# main.net
KiCad netlist of a schematic drawn in Altium Designer
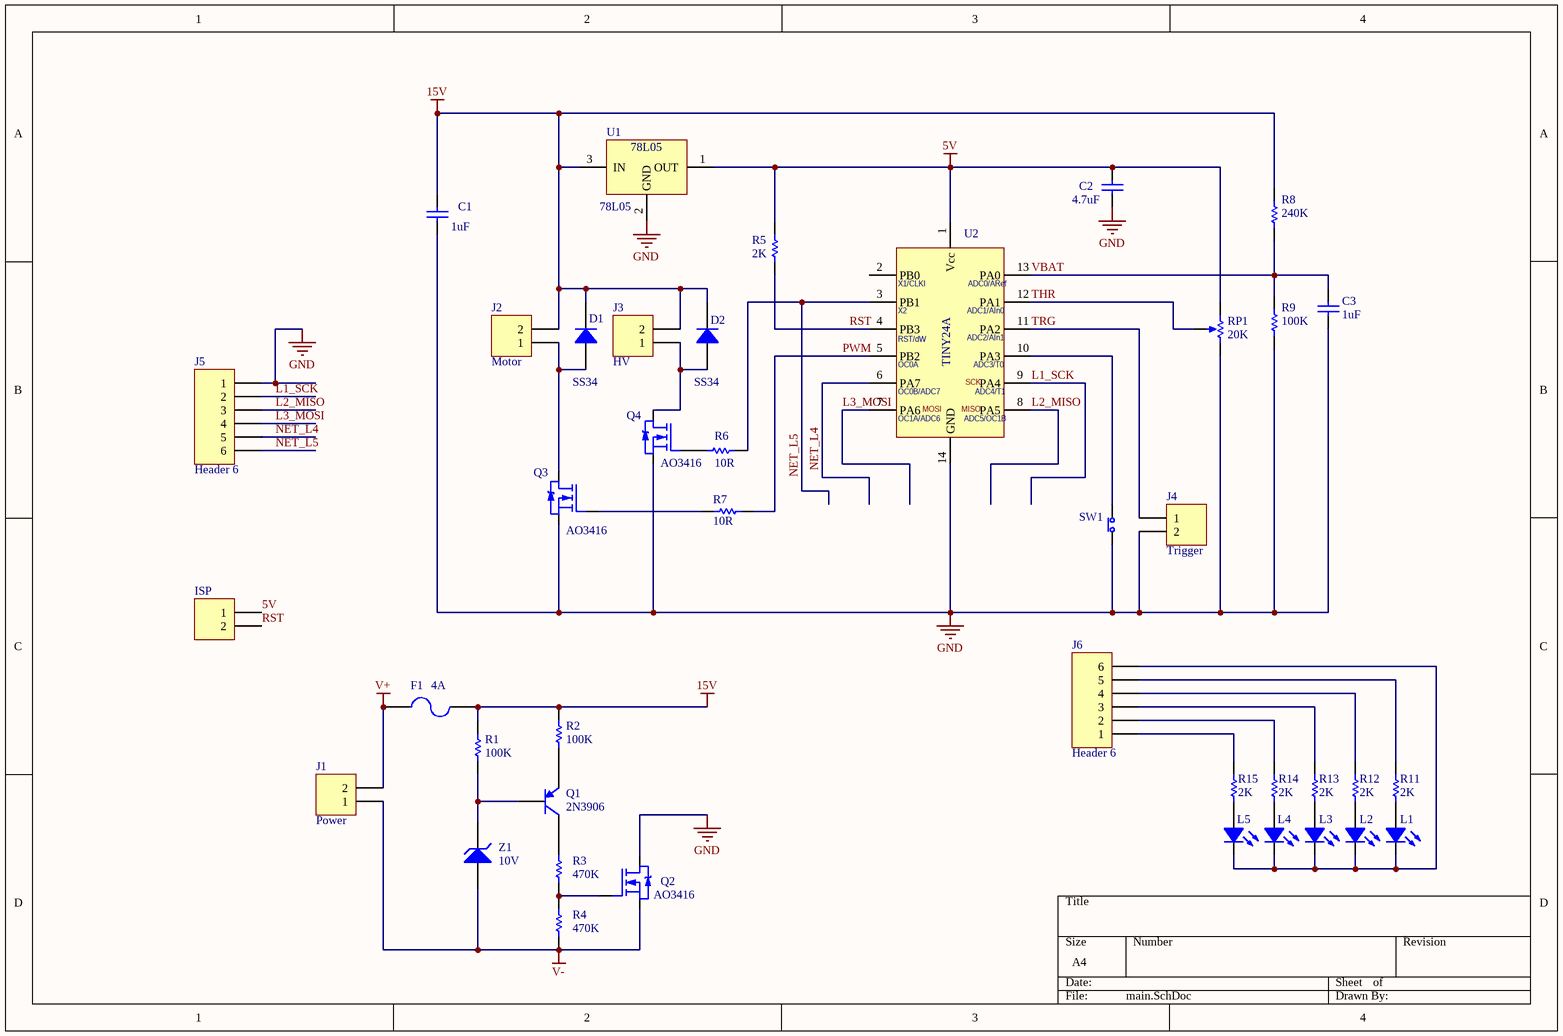
[diagram p0: main.SchDoc]

(export (version "E")
  (design (tool "Eeschema 10.0.6"))
  (components
    (comp (ref "C1")
      (value "1uF")
      (footprint "CAP0805")
      (description "贴片电容")
      (fields (field (name "Comment") "Cap") (field (name "PUBLISHER") "Altium Limited"))
      (libsource (lib "Miscellaneous Devices") (part "Cap"))
    )
    (comp (ref "C2")
      (value "4.7uF")
      (footprint "CAP0805")
      (description "贴片电容")
      (fields (field (name "Comment") "Cap") (field (name "PUBLISHER") "Altium Limited"))
      (libsource (lib "Miscellaneous Devices") (part "Cap"))
    )
    (comp (ref "C3")
      (value "1uF")
      (footprint "CAP0805")
      (description "贴片电容")
      (fields (field (name "Comment") "Cap") (field (name "PUBLISHER") "Altium Limited"))
      (libsource (lib "Miscellaneous Devices") (part "Cap"))
    )
    (comp (ref "D1")
      (value "SS34")
      (footprint "DO214A")
      (description "贴片二极管")
      (fields (field (name "PUBLISHER") "Altium Limited"))
      (libsource (lib "nizn") (part "Diode"))
    )
    (comp (ref "D2")
      (value "SS34")
      (footprint "DO214A")
      (description "贴片二极管")
      (fields (field (name "PUBLISHER") "Altium Limited"))
      (libsource (lib "nizn") (part "Diode"))
    )
    (comp (ref "F1")
      (value "4A")
      (footprint "FUSE1206")
      (description "贴片熔断型保险丝")
      (fields (field (name "PUBLISHER") "Altium Limited"))
      (libsource (lib "pumpctrl") (part "Fuse 2"))
    )
    (comp (ref "ISP")
      (value "~")
      (footprint "HDR1X2")
      (description "空")
      (fields (field (name "PUBLISHER") "Altium Limited"))
      (libsource (lib "Miscellaneous Connectors") (part "Header 2"))
    )
    (comp (ref "J1")
      (value "Power")
      (footprint "JST2")
      (description "JST 2P 插座")
      (fields (field (name "PUBLISHER") "Altium Limited"))
      (libsource (lib "") (part "Header 2_1"))
    )
    (comp (ref "J2")
      (value "Motor")
      (footprint "JST2")
      (description "JST 2P 插座")
      (fields (field (name "PUBLISHER") "Altium Limited"))
      (libsource (lib "") (part "Header 2_1"))
    )
    (comp (ref "J3")
      (value "HV")
      (footprint "JST2")
      (description "JST 2P 插座")
      (fields (field (name "PUBLISHER") "Altium Limited"))
      (libsource (lib "") (part "Header 2_1"))
    )
    (comp (ref "J4")
      (value "Trigger")
      (footprint "JST2")
      (description "JST 2P 插座")
      (fields (field (name "PUBLISHER") "Altium Limited"))
      (libsource (lib "") (part "Header 2_2"))
    )
    (comp (ref "J5")
      (value "Header 6")
      (footprint "HDR125_6W")
      (description "1.25mm 6P 插座")
      (fields (field (name "PUBLISHER") "Altium Limited"))
      (libsource (lib "Miscellaneous Connectors") (part "Header 6"))
    )
    (comp (ref "J6")
      (value "Header 6")
      (footprint "HDR125_6W")
      (description "1.25mm 6P 插座")
      (fields (field (name "PUBLISHER") "Altium Limited"))
      (libsource (lib "") (part "Header 6_1"))
    )
    (comp (ref "L1")
      (value "高亮翠绿")
      (footprint "LED2G_SLIM")
      (description "贴片LED 0805")
      (fields (field (name "PUBLISHER") "Altium Limited"))
      (libsource (lib "pumpctrl") (part "LED"))
    )
    (comp (ref "L2")
      (value "高亮翠绿")
      (footprint "LED2G_SLIM")
      (description "贴片LED 0805")
      (fields (field (name "PUBLISHER") "Altium Limited"))
      (libsource (lib "pumpctrl") (part "LED"))
    )
    (comp (ref "L3")
      (value "高亮翠绿")
      (footprint "LED2G_SLIM")
      (description "贴片LED 0805")
      (fields (field (name "PUBLISHER") "Altium Limited"))
      (libsource (lib "pumpctrl") (part "LED"))
    )
    (comp (ref "L4")
      (value "高亮翠绿")
      (footprint "LED2G_SLIM")
      (description "贴片LED 0805")
      (fields (field (name "PUBLISHER") "Altium Limited"))
      (libsource (lib "pumpctrl") (part "LED"))
    )
    (comp (ref "L5")
      (value "高亮蓝色")
      (footprint "LED2R_SLIM")
      (description "贴片LED 0805")
      (fields (field (name "PUBLISHER") "Altium Limited"))
      (libsource (lib "pumpctrl") (part "LED"))
    )
    (comp (ref "Q1")
      (value "2N3906")
      (footprint "SOT23_CBE")
      (description "PNP General Purpose Amplifier")
      (fields (field (name "PUBLISHER") "Altium Limited"))
      (libsource (lib "pumpctrl") (part "PNP"))
    )
    (comp (ref "Q2")
      (value "AO3416")
      (footprint "SOT23_NMOS")
      (description "MOSFET N")
      (fields (field (name "PUBLISHER") "Altium Limited"))
      (libsource (lib "pumpctrl") (part "NMOS"))
    )
    (comp (ref "Q3")
      (value "AO3416")
      (footprint "SOT23_NMOS")
      (description "MOSFET N")
      (fields (field (name "PUBLISHER") "Altium Limited"))
      (libsource (lib "pumpctrl") (part "NMOS"))
    )
    (comp (ref "Q4")
      (value "AO3416")
      (footprint "SOT23_NMOS")
      (description "MOSFET N")
      (fields (field (name "PUBLISHER") "Altium Limited"))
      (libsource (lib "pumpctrl") (part "NMOS"))
    )
    (comp (ref "R1")
      (value "100K")
      (footprint "RES0805")
      (description "贴片电阻")
      (fields (field (name "Comment") "Res1") (field (name "PUBLISHER") "Altium Limited"))
      (libsource (lib "Miscellaneous Devices") (part "Res1"))
    )
    (comp (ref "R2")
      (value "100K")
      (footprint "RES0805")
      (description "贴片电阻")
      (fields (field (name "Comment") "Res1") (field (name "PUBLISHER") "Altium Limited"))
      (libsource (lib "Miscellaneous Devices") (part "Res1"))
    )
    (comp (ref "R3")
      (value "470K")
      (footprint "RES0805")
      (description "贴片电阻")
      (fields (field (name "Comment") "Res1") (field (name "PUBLISHER") "Altium Limited"))
      (libsource (lib "Miscellaneous Devices") (part "Res1"))
    )
    (comp (ref "R4")
      (value "470K")
      (footprint "RES0805")
      (description "贴片电阻")
      (fields (field (name "Comment") "Res1") (field (name "PUBLISHER") "Altium Limited"))
      (libsource (lib "Miscellaneous Devices") (part "Res1"))
    )
    (comp (ref "R5")
      (value "2K")
      (footprint "RES0805")
      (description "贴片电阻")
      (fields (field (name "Comment") "Res1") (field (name "PUBLISHER") "Altium Limited"))
      (libsource (lib "Miscellaneous Devices") (part "Res1"))
    )
    (comp (ref "R6")
      (value "10R")
      (footprint "RES0805")
      (description "贴片电阻")
      (fields (field (name "Comment") "Res1") (field (name "PUBLISHER") "Altium Limited"))
      (libsource (lib "Miscellaneous Devices") (part "Res1"))
    )
    (comp (ref "R7")
      (value "10R")
      (footprint "RES0805")
      (description "贴片电阻")
      (fields (field (name "Comment") "Res1") (field (name "PUBLISHER") "Altium Limited"))
      (libsource (lib "Miscellaneous Devices") (part "Res1"))
    )
    (comp (ref "R8")
      (value "240K")
      (footprint "RES0805")
      (description "贴片电阻")
      (fields (field (name "Comment") "Res1") (field (name "PUBLISHER") "Altium Limited"))
      (libsource (lib "Miscellaneous Devices") (part "Res1"))
    )
    (comp (ref "R9")
      (value "100K")
      (footprint "RES0805")
      (description "贴片电阻")
      (fields (field (name "Comment") "Res1") (field (name "PUBLISHER") "Altium Limited"))
      (libsource (lib "Miscellaneous Devices") (part "Res1"))
    )
    (comp (ref "R11")
      (value "2K")
      (footprint "RES0805")
      (description "贴片电阻")
      (fields (field (name "Comment") "Res1") (field (name "PUBLISHER") "Altium Limited"))
      (libsource (lib "Miscellaneous Devices") (part "Res1"))
    )
    (comp (ref "R12")
      (value "2K")
      (footprint "RES0805")
      (description "贴片电阻")
      (fields (field (name "Comment") "Res1") (field (name "PUBLISHER") "Altium Limited"))
      (libsource (lib "Miscellaneous Devices") (part "Res1"))
    )
    (comp (ref "R13")
      (value "2K")
      (footprint "RES0805")
      (description "贴片电阻")
      (fields (field (name "Comment") "Res1") (field (name "PUBLISHER") "Altium Limited"))
      (libsource (lib "Miscellaneous Devices") (part "Res1"))
    )
    (comp (ref "R14")
      (value "2K")
      (footprint "RES0805")
      (description "贴片电阻")
      (fields (field (name "Comment") "Res1") (field (name "PUBLISHER") "Altium Limited"))
      (libsource (lib "Miscellaneous Devices") (part "Res1"))
    )
    (comp (ref "R15")
      (value "2K")
      (footprint "RES0805")
      (description "贴片电阻")
      (fields (field (name "Comment") "Res1") (field (name "PUBLISHER") "Altium Limited"))
      (libsource (lib "Miscellaneous Devices") (part "Res1"))
    )
    (comp (ref "RP1")
      (value "20K")
      (footprint "POT_RV09")
      (description "Potentiometer")
      (fields (field (name "Comment") "RPot") (field (name "PUBLISHER") "Altium Limited"))
      (libsource (lib "Miscellaneous Devices") (part "RPot"))
    )
    (comp (ref "SW1")
      (value "~")
      (footprint "TACT2")
      (description "轻触开关")
      (fields (field (name "PUBLISHER") "Altium Limited"))
      (libsource (lib "pumpctrl") (part "JP2"))
    )
    (comp (ref "U1")
      (value "78L05")
      (footprint "SOT89_VREG")
      (description "三端稳压贴片")
      (fields (field (name "PUBLISHER") "Altium Limited"))
      (libsource (lib "magcontrol") (part "78L05"))
    )
    (comp (ref "U2")
      (value "TINY24A")
      (footprint "SO14")
      (description "集成电路")
      (libsource (lib "nizn") (part "TINY13A"))
    )
    (comp (ref "Z1")
      (value "10V")
      (footprint "1N4148SMT")
      (description "Zener Diode")
      (fields (field (name "PUBLISHER") "Altium Limited"))
      (libsource (lib "Miscellaneous Devices") (part "D Zener"))
    )
  )
  (nets
    (net (code "1") (name "/L1_SCK") (class "Default")
      (node (ref "J5") (pin "2") (pinfunction "2_2") (pintype "passive"))
      (node (ref "U2") (pin "9") (pinfunction "PA4_9") (pintype "power_in"))
    )
    (net (code "2") (name "/L2_MISO") (class "Default")
      (node (ref "J5") (pin "3") (pinfunction "3_3") (pintype "passive"))
      (node (ref "U2") (pin "8") (pinfunction "PA5_8") (pintype "power_in"))
    )
    (net (code "3") (name "/L3_MOSI") (class "Default")
      (node (ref "J5") (pin "4") (pinfunction "4_4") (pintype "passive"))
      (node (ref "U2") (pin "7") (pinfunction "PA6_7") (pintype "power_in"))
    )
    (net (code "4") (name "/NET_L4") (class "Default")
      (node (ref "J5") (pin "5") (pinfunction "5_5") (pintype "passive"))
      (node (ref "U2") (pin "6") (pinfunction "PA7_6") (pintype "power_in"))
    )
    (net (code "5") (name "/NET_L5") (class "Default")
      (node (ref "J5") (pin "6") (pinfunction "6_6") (pintype "passive"))
      (node (ref "R6") (pin "1") (pinfunction "1_1") (pintype "passive"))
      (node (ref "U2") (pin "3") (pinfunction "PB1_3") (pintype "power_in"))
    )
    (net (code "6") (name "/PWM") (class "Default")
      (node (ref "R7") (pin "2") (pinfunction "2_2") (pintype "passive"))
      (node (ref "U2") (pin "5") (pinfunction "PB2_5") (pintype "power_in"))
    )
    (net (code "7") (name "/RST") (class "Default")
      (node (ref "ISP") (pin "2") (pinfunction "2_2") (pintype "passive"))
      (node (ref "R5") (pin "1") (pinfunction "1_1") (pintype "passive"))
      (node (ref "U2") (pin "4") (pinfunction "PB3_4") (pintype "power_in"))
    )
    (net (code "8") (name "/THR") (class "Default")
      (node (ref "RP1") (pin "3") (pinfunction "TAP_3") (pintype "passive"))
      (node (ref "U2") (pin "12") (pinfunction "PA1_12") (pintype "power_in"))
    )
    (net (code "9") (name "/TRG") (class "Default")
      (node (ref "J4") (pin "1") (pinfunction "1_1") (pintype "passive"))
      (node (ref "U2") (pin "11") (pinfunction "PA2_11") (pintype "power_in"))
    )
    (net (code "10") (name "/VBAT") (class "Default")
      (node (ref "C3") (pin "2") (pinfunction "2_2") (pintype "passive"))
      (node (ref "R8") (pin "1") (pinfunction "1_1") (pintype "passive"))
      (node (ref "R9") (pin "2") (pinfunction "2_2") (pintype "passive"))
      (node (ref "U2") (pin "13") (pinfunction "PA0_13") (pintype "power_in"))
    )
    (net (code "11") (name "5V") (class "Default")
      (node (ref "C2") (pin "2") (pinfunction "2_2") (pintype "passive"))
      (node (ref "ISP") (pin "1") (pinfunction "1_1") (pintype "passive"))
      (node (ref "R5") (pin "2") (pinfunction "2_2") (pintype "passive"))
      (node (ref "RP1") (pin "1") (pinfunction "TOP_1") (pintype "passive"))
      (node (ref "U1") (pin "1") (pinfunction "OUT_1") (pintype "power_in"))
      (node (ref "U2") (pin "1") (pinfunction "Vcc_1") (pintype "power_in"))
    )
    (net (code "12") (name "15V") (class "Default")
      (node (ref "C1") (pin "2") (pinfunction "2_2") (pintype "passive"))
      (node (ref "D1") (pin "2") (pinfunction "K_2") (pintype "passive"))
      (node (ref "D2") (pin "2") (pinfunction "K_2") (pintype "passive"))
      (node (ref "F1") (pin "1") (pinfunction "1_1") (pintype "passive"))
      (node (ref "J2") (pin "2") (pinfunction "2_2") (pintype "passive"))
      (node (ref "J3") (pin "2") (pinfunction "2_2") (pintype "passive"))
      (node (ref "R1") (pin "1") (pinfunction "1_1") (pintype "passive"))
      (node (ref "R2") (pin "1") (pinfunction "1_1") (pintype "passive"))
      (node (ref "R8") (pin "2") (pinfunction "2_2") (pintype "passive"))
      (node (ref "U1") (pin "3") (pinfunction "IN_3") (pintype "power_in"))
    )
    (net (code "13") (name "GND") (class "Default")
      (node (ref "C1") (pin "1") (pinfunction "1_1") (pintype "passive"))
      (node (ref "C2") (pin "1") (pinfunction "1_1") (pintype "passive"))
      (node (ref "C3") (pin "1") (pinfunction "1_1") (pintype "passive"))
      (node (ref "J4") (pin "2") (pinfunction "2_2") (pintype "passive"))
      (node (ref "J5") (pin "1") (pinfunction "1_1") (pintype "passive"))
      (node (ref "Q2") (pin "D") (pinfunction "D_D") (pintype "passive"))
      (node (ref "Q3") (pin "S") (pinfunction "S_S") (pintype "passive"))
      (node (ref "Q4") (pin "S") (pinfunction "S_S") (pintype "passive"))
      (node (ref "R9") (pin "1") (pinfunction "1_1") (pintype "passive"))
      (node (ref "RP1") (pin "2") (pinfunction "BOT_2") (pintype "passive"))
      (node (ref "SW1") (pin "1") (pinfunction "1_1") (pintype "passive"))
      (node (ref "U1") (pin "2") (pinfunction "GND_2") (pintype "power_in"))
      (node (ref "U2") (pin "14") (pinfunction "GND_14") (pintype "power_in"))
    )
    (net (code "14") (name "Net-(D1-A)") (class "Default")
      (node (ref "D1") (pin "1") (pinfunction "A_1") (pintype "passive"))
      (node (ref "J2") (pin "1") (pinfunction "1_1") (pintype "passive"))
      (node (ref "Q3") (pin "D") (pinfunction "D_D") (pintype "passive"))
    )
    (net (code "15") (name "Net-(D2-A)") (class "Default")
      (node (ref "D2") (pin "1") (pinfunction "A_1") (pintype "passive"))
      (node (ref "J3") (pin "1") (pinfunction "1_1") (pintype "passive"))
      (node (ref "Q4") (pin "D") (pinfunction "D_D") (pintype "passive"))
    )
    (net (code "16") (name "Net-(J6-Pad1)") (class "Default")
      (node (ref "J6") (pin "1") (pinfunction "1_1") (pintype "passive"))
      (node (ref "R15") (pin "1") (pinfunction "1_1") (pintype "passive"))
    )
    (net (code "17") (name "Net-(J6-Pad2)") (class "Default")
      (node (ref "J6") (pin "2") (pinfunction "2_2") (pintype "passive"))
      (node (ref "R14") (pin "1") (pinfunction "1_1") (pintype "passive"))
    )
    (net (code "18") (name "Net-(J6-Pad3)") (class "Default")
      (node (ref "J6") (pin "3") (pinfunction "3_3") (pintype "passive"))
      (node (ref "R13") (pin "1") (pinfunction "1_1") (pintype "passive"))
    )
    (net (code "19") (name "Net-(J6-Pad4)") (class "Default")
      (node (ref "J6") (pin "4") (pinfunction "4_4") (pintype "passive"))
      (node (ref "R12") (pin "1") (pinfunction "1_1") (pintype "passive"))
    )
    (net (code "20") (name "Net-(J6-Pad5)") (class "Default")
      (node (ref "J6") (pin "5") (pinfunction "5_5") (pintype "passive"))
      (node (ref "R11") (pin "1") (pinfunction "1_1") (pintype "passive"))
    )
    (net (code "21") (name "Net-(L1-A)") (class "Default")
      (node (ref "L1") (pin "1") (pinfunction "A_1") (pintype "passive"))
      (node (ref "R11") (pin "2") (pinfunction "2_2") (pintype "passive"))
    )
    (net (code "22") (name "Net-(L1-K)") (class "Default")
      (node (ref "J6") (pin "6") (pinfunction "6_6") (pintype "passive"))
      (node (ref "L1") (pin "2") (pinfunction "K_2") (pintype "passive"))
      (node (ref "L2") (pin "2") (pinfunction "K_2") (pintype "passive"))
      (node (ref "L3") (pin "2") (pinfunction "K_2") (pintype "passive"))
      (node (ref "L4") (pin "2") (pinfunction "K_2") (pintype "passive"))
      (node (ref "L5") (pin "2") (pinfunction "K_2") (pintype "passive"))
    )
    (net (code "23") (name "Net-(L2-A)") (class "Default")
      (node (ref "L2") (pin "1") (pinfunction "A_1") (pintype "passive"))
      (node (ref "R12") (pin "2") (pinfunction "2_2") (pintype "passive"))
    )
    (net (code "24") (name "Net-(L3-A)") (class "Default")
      (node (ref "L3") (pin "1") (pinfunction "A_1") (pintype "passive"))
      (node (ref "R13") (pin "2") (pinfunction "2_2") (pintype "passive"))
    )
    (net (code "25") (name "Net-(L4-A)") (class "Default")
      (node (ref "L4") (pin "1") (pinfunction "A_1") (pintype "passive"))
      (node (ref "R14") (pin "2") (pinfunction "2_2") (pintype "passive"))
    )
    (net (code "26") (name "Net-(L5-A)") (class "Default")
      (node (ref "L5") (pin "1") (pinfunction "A_1") (pintype "passive"))
      (node (ref "R15") (pin "2") (pinfunction "2_2") (pintype "passive"))
    )
    (net (code "27") (name "Net-(Q1-PadC)") (class "Default")
      (node (ref "Q1") (pin "C") (pinfunction "C_C") (pintype "passive"))
      (node (ref "R3") (pin "1") (pinfunction "1_1") (pintype "passive"))
    )
    (net (code "28") (name "Net-(Q1-PadE)") (class "Default")
      (node (ref "Q1") (pin "E") (pinfunction "E_E") (pintype "passive"))
      (node (ref "R2") (pin "2") (pinfunction "2_2") (pintype "passive"))
    )
    (net (code "29") (name "Net-(Q2-PadG)") (class "Default")
      (node (ref "Q2") (pin "G") (pinfunction "G_G") (pintype "passive"))
      (node (ref "R3") (pin "2") (pinfunction "2_2") (pintype "passive"))
      (node (ref "R4") (pin "1") (pinfunction "1_1") (pintype "passive"))
    )
    (net (code "30") (name "Net-(Q3-PadG)") (class "Default")
      (node (ref "Q3") (pin "G") (pinfunction "G_G") (pintype "passive"))
      (node (ref "R7") (pin "1") (pinfunction "1_1") (pintype "passive"))
    )
    (net (code "31") (name "Net-(Q4-PadG)") (class "Default")
      (node (ref "Q4") (pin "G") (pinfunction "G_G") (pintype "passive"))
      (node (ref "R6") (pin "2") (pinfunction "2_2") (pintype "passive"))
    )
    (net (code "32") (name "Net-(U2-PA3)") (class "Default")
      (node (ref "SW1") (pin "2") (pinfunction "2_2") (pintype "passive"))
      (node (ref "U2") (pin "10") (pinfunction "PA3_10") (pintype "power_in"))
    )
    (net (code "33") (name "Net-(Z1-K)") (class "Default")
      (node (ref "Q1") (pin "B") (pinfunction "B_B") (pintype "passive"))
      (node (ref "R1") (pin "2") (pinfunction "2_2") (pintype "passive"))
      (node (ref "Z1") (pin "2") (pinfunction "K_2") (pintype "passive"))
    )
    (net (code "34") (name "V+") (class "Default")
      (node (ref "F1") (pin "2") (pinfunction "2_2") (pintype "passive"))
      (node (ref "J1") (pin "2") (pinfunction "2_2") (pintype "passive"))
    )
    (net (code "35") (name "V-") (class "Default")
      (node (ref "J1") (pin "1") (pinfunction "1_1") (pintype "passive"))
      (node (ref "Q2") (pin "S") (pinfunction "S_S") (pintype "passive"))
      (node (ref "R4") (pin "2") (pinfunction "2_2") (pintype "passive"))
      (node (ref "Z1") (pin "1") (pinfunction "A_1") (pintype "passive"))
    )
    (net (code "36") (name "unconnected-(U2-PB0-Pad2)") (class "Default")
      (node (ref "U2") (pin "2") (pinfunction "PB0_2") (pintype "power_in"))
    )
  )
)
